# LED.net
KiCad netlist of a schematic drawn in EAGLE
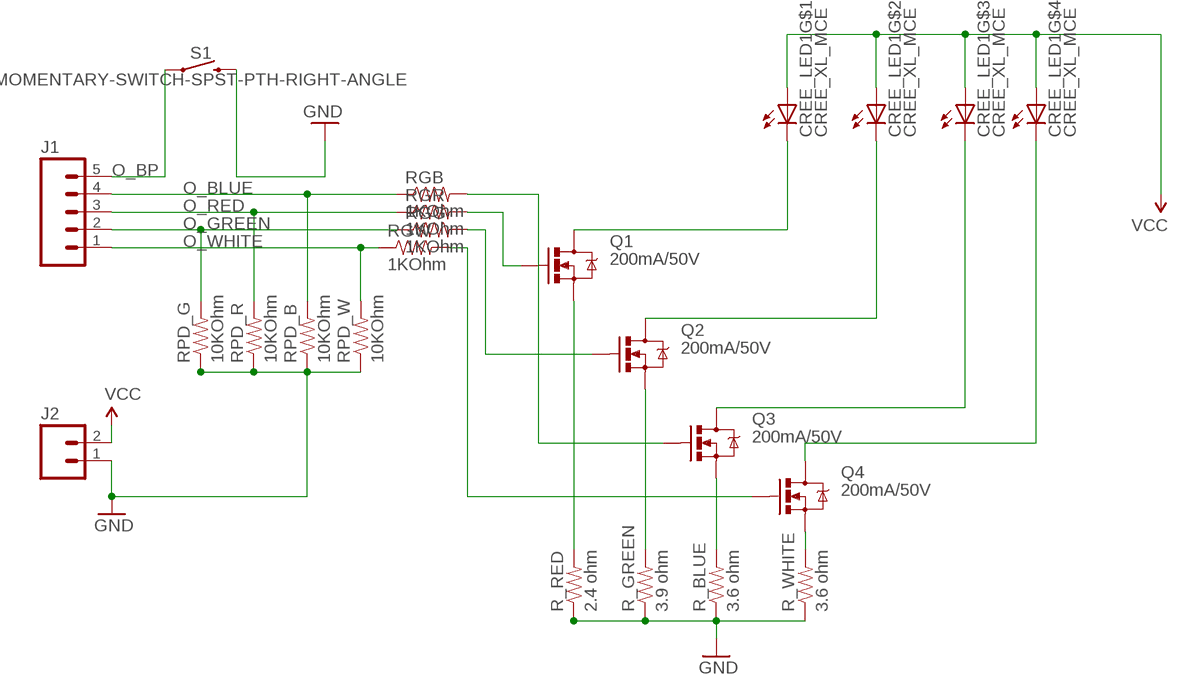
[diagram p0: schematic, sheet 1]

(export (version "E")
  (design (tool "Eeschema 10.0.6"))
  (components
    (comp (ref "CREE_LED1")
      (value "CREE_XL_MCE")
      (footprint "eagle-import:CREE_XL_MCE")
      (libsource (lib "eagle-import") (part "CREE_XL_MCE"))
    )
    (comp (ref "J1")
      (value "M05NO_SILK")
      (footprint "eagle-import:1X05_NO_SILK")
      (libsource (lib "eagle-import") (part "M05NO_SILK"))
    )
    (comp (ref "J2")
      (value "M021X02_NO_SILK")
      (footprint "eagle-import:1X02_NO_SILK")
      (libsource (lib "eagle-import") (part "M021X02_NO_SILK"))
    )
    (comp (ref "Q1")
      (value "200mA/50V")
      (footprint "eagle-import:SOT23-3")
      (libsource (lib "eagle-import") (part "MOSFET-NCHANNELBSS138"))
    )
    (comp (ref "Q2")
      (value "200mA/50V")
      (footprint "eagle-import:SOT23-3")
      (libsource (lib "eagle-import") (part "MOSFET-NCHANNELBSS138"))
    )
    (comp (ref "Q3")
      (value "200mA/50V")
      (footprint "eagle-import:SOT23-3")
      (libsource (lib "eagle-import") (part "MOSFET-NCHANNELBSS138"))
    )
    (comp (ref "Q4")
      (value "200mA/50V")
      (footprint "eagle-import:SOT23-3")
      (libsource (lib "eagle-import") (part "MOSFET-NCHANNELBSS138"))
    )
    (comp (ref "RGB")
      (value "1KOhm")
      (footprint "eagle-import:0805")
      (libsource (lib "eagle-import") (part "RESISTOR0805-RES"))
    )
    (comp (ref "RGG")
      (value "1KOhm")
      (footprint "eagle-import:0805")
      (libsource (lib "eagle-import") (part "RESISTOR0805-RES"))
    )
    (comp (ref "RGR")
      (value "1KOhm")
      (footprint "eagle-import:0805")
      (libsource (lib "eagle-import") (part "RESISTOR0805-RES"))
    )
    (comp (ref "RGW")
      (value "1KOhm")
      (footprint "eagle-import:0805")
      (libsource (lib "eagle-import") (part "RESISTOR0805-RES"))
    )
    (comp (ref "RPD_B")
      (value "10KOhm")
      (footprint "eagle-import:0805")
      (libsource (lib "eagle-import") (part "RESISTOR0805-RES"))
    )
    (comp (ref "RPD_G")
      (value "10KOhm")
      (footprint "eagle-import:0805")
      (libsource (lib "eagle-import") (part "RESISTOR0805-RES"))
    )
    (comp (ref "RPD_R")
      (value "10KOhm")
      (footprint "eagle-import:0805")
      (libsource (lib "eagle-import") (part "RESISTOR0805-RES"))
    )
    (comp (ref "RPD_W")
      (value "10KOhm")
      (footprint "eagle-import:0805")
      (libsource (lib "eagle-import") (part "RESISTOR0805-RES"))
    )
    (comp (ref "R_BLUE")
      (value "3.6 ohm")
      (footprint "eagle-import:0805")
      (libsource (lib "eagle-import") (part "RESISTOR0805-RES"))
    )
    (comp (ref "R_GREEN")
      (value "3.9 ohm")
      (footprint "eagle-import:0805")
      (libsource (lib "eagle-import") (part "RESISTOR0805-RES"))
    )
    (comp (ref "R_RED")
      (value "2.4 ohm")
      (footprint "eagle-import:0805")
      (libsource (lib "eagle-import") (part "RESISTOR0805-RES"))
    )
    (comp (ref "R_WHITE")
      (value "3.6 ohm")
      (footprint "eagle-import:0805")
      (libsource (lib "eagle-import") (part "RESISTOR0805-RES"))
    )
    (comp (ref "S1")
      (value "MOMENTARY-SWITCH-SPST-PTH-RIGHT-ANGLE")
      (footprint "eagle-import:TACTILE_SWITCH_PTH_RIGHT_ANGLE")
      (libsource (lib "eagle-import") (part "MOMENTARY-SWITCH-SPST-PTH-RIGHT-ANGLE"))
    )
  )
  (nets
    (net (code "1") (name "/O_BLUE") (class "Default")
      (node (ref "J1") (pin "4") (pinfunction "4_4") (pintype "passive"))
      (node (ref "RGB") (pin "1") (pinfunction "1_1") (pintype "passive"))
      (node (ref "RPD_B") (pin "2") (pinfunction "2_2") (pintype "passive"))
    )
    (net (code "2") (name "/O_BP") (class "Default")
      (node (ref "J1") (pin "5") (pinfunction "5_5") (pintype "passive"))
      (node (ref "S1") (pin "1") (pinfunction "1_1") (pintype "passive"))
    )
    (net (code "3") (name "/O_GREEN") (class "Default")
      (node (ref "J1") (pin "2") (pinfunction "2_2") (pintype "passive"))
      (node (ref "RGG") (pin "1") (pinfunction "1_1") (pintype "passive"))
      (node (ref "RPD_G") (pin "2") (pinfunction "2_2") (pintype "passive"))
    )
    (net (code "4") (name "/O_RED") (class "Default")
      (node (ref "J1") (pin "3") (pinfunction "3_3") (pintype "passive"))
      (node (ref "RGR") (pin "1") (pinfunction "1_1") (pintype "passive"))
      (node (ref "RPD_R") (pin "2") (pinfunction "2_2") (pintype "passive"))
    )
    (net (code "5") (name "/O_WHITE") (class "Default")
      (node (ref "J1") (pin "1") (pinfunction "1_1") (pintype "passive"))
      (node (ref "RGW") (pin "1") (pinfunction "1_1") (pintype "passive"))
      (node (ref "RPD_W") (pin "2") (pinfunction "2_2") (pintype "passive"))
    )
    (net (code "6") (name "GND") (class "Default")
      (node (ref "J2") (pin "1") (pinfunction "1_1") (pintype "passive"))
      (node (ref "RPD_B") (pin "1") (pinfunction "1_1") (pintype "passive"))
      (node (ref "RPD_G") (pin "1") (pinfunction "1_1") (pintype "passive"))
      (node (ref "RPD_R") (pin "1") (pinfunction "1_1") (pintype "passive"))
      (node (ref "RPD_W") (pin "1") (pinfunction "1_1") (pintype "passive"))
      (node (ref "R_BLUE") (pin "1") (pinfunction "1_1") (pintype "passive"))
      (node (ref "R_GREEN") (pin "1") (pinfunction "1_1") (pintype "passive"))
      (node (ref "R_RED") (pin "1") (pinfunction "1_1") (pintype "passive"))
      (node (ref "R_WHITE") (pin "1") (pinfunction "1_1") (pintype "passive"))
      (node (ref "S1") (pin "2") (pinfunction "2_2") (pintype "passive"))
    )
    (net (code "7") (name "Net-(CREE_LED1A-C)") (class "Default")
      (node (ref "CREE_LED1") (pin "8") (pinfunction "C_8") (pintype "passive"))
      (node (ref "Q1") (pin "3") (pinfunction "D_3") (pintype "passive"))
    )
    (net (code "8") (name "Net-(CREE_LED1B-C)") (class "Default")
      (node (ref "CREE_LED1") (pin "7") (pinfunction "C_7") (pintype "passive"))
      (node (ref "Q2") (pin "3") (pinfunction "D_3") (pintype "passive"))
    )
    (net (code "9") (name "Net-(CREE_LED1C-C)") (class "Default")
      (node (ref "CREE_LED1") (pin "6") (pinfunction "C_6") (pintype "passive"))
      (node (ref "Q3") (pin "3") (pinfunction "D_3") (pintype "passive"))
    )
    (net (code "10") (name "Net-(CREE_LED1D-C)") (class "Default")
      (node (ref "CREE_LED1") (pin "5") (pinfunction "C_5") (pintype "passive"))
      (node (ref "Q4") (pin "3") (pinfunction "D_3") (pintype "passive"))
    )
    (net (code "11") (name "Net-(Q1-G)") (class "Default")
      (node (ref "Q1") (pin "1") (pinfunction "G_1") (pintype "passive"))
      (node (ref "RGR") (pin "2") (pinfunction "2_2") (pintype "passive"))
    )
    (net (code "12") (name "Net-(Q1-S)") (class "Default")
      (node (ref "Q1") (pin "2") (pinfunction "S_2") (pintype "passive"))
      (node (ref "R_RED") (pin "2") (pinfunction "2_2") (pintype "passive"))
    )
    (net (code "13") (name "Net-(Q2-G)") (class "Default")
      (node (ref "Q2") (pin "1") (pinfunction "G_1") (pintype "passive"))
      (node (ref "RGG") (pin "2") (pinfunction "2_2") (pintype "passive"))
    )
    (net (code "14") (name "Net-(Q2-S)") (class "Default")
      (node (ref "Q2") (pin "2") (pinfunction "S_2") (pintype "passive"))
      (node (ref "R_GREEN") (pin "2") (pinfunction "2_2") (pintype "passive"))
    )
    (net (code "15") (name "Net-(Q3-G)") (class "Default")
      (node (ref "Q3") (pin "1") (pinfunction "G_1") (pintype "passive"))
      (node (ref "RGB") (pin "2") (pinfunction "2_2") (pintype "passive"))
    )
    (net (code "16") (name "Net-(Q3-S)") (class "Default")
      (node (ref "Q3") (pin "2") (pinfunction "S_2") (pintype "passive"))
      (node (ref "R_BLUE") (pin "2") (pinfunction "2_2") (pintype "passive"))
    )
    (net (code "17") (name "Net-(Q4-G)") (class "Default")
      (node (ref "Q4") (pin "1") (pinfunction "G_1") (pintype "passive"))
      (node (ref "RGW") (pin "2") (pinfunction "2_2") (pintype "passive"))
    )
    (net (code "18") (name "Net-(Q4-S)") (class "Default")
      (node (ref "Q4") (pin "2") (pinfunction "S_2") (pintype "passive"))
      (node (ref "R_WHITE") (pin "2") (pinfunction "2_2") (pintype "passive"))
    )
    (net (code "19") (name "VCC") (class "Default")
      (node (ref "CREE_LED1") (pin "1") (pinfunction "A_1") (pintype "passive"))
      (node (ref "CREE_LED1") (pin "2") (pinfunction "A_2") (pintype "passive"))
      (node (ref "CREE_LED1") (pin "3") (pinfunction "A_3") (pintype "passive"))
      (node (ref "CREE_LED1") (pin "4") (pinfunction "A_4") (pintype "passive"))
      (node (ref "J2") (pin "2") (pinfunction "2_2") (pintype "passive"))
    )
  )
)
